# WattMeter_v3.net
KiCad netlist of a schematic drawn in EAGLE
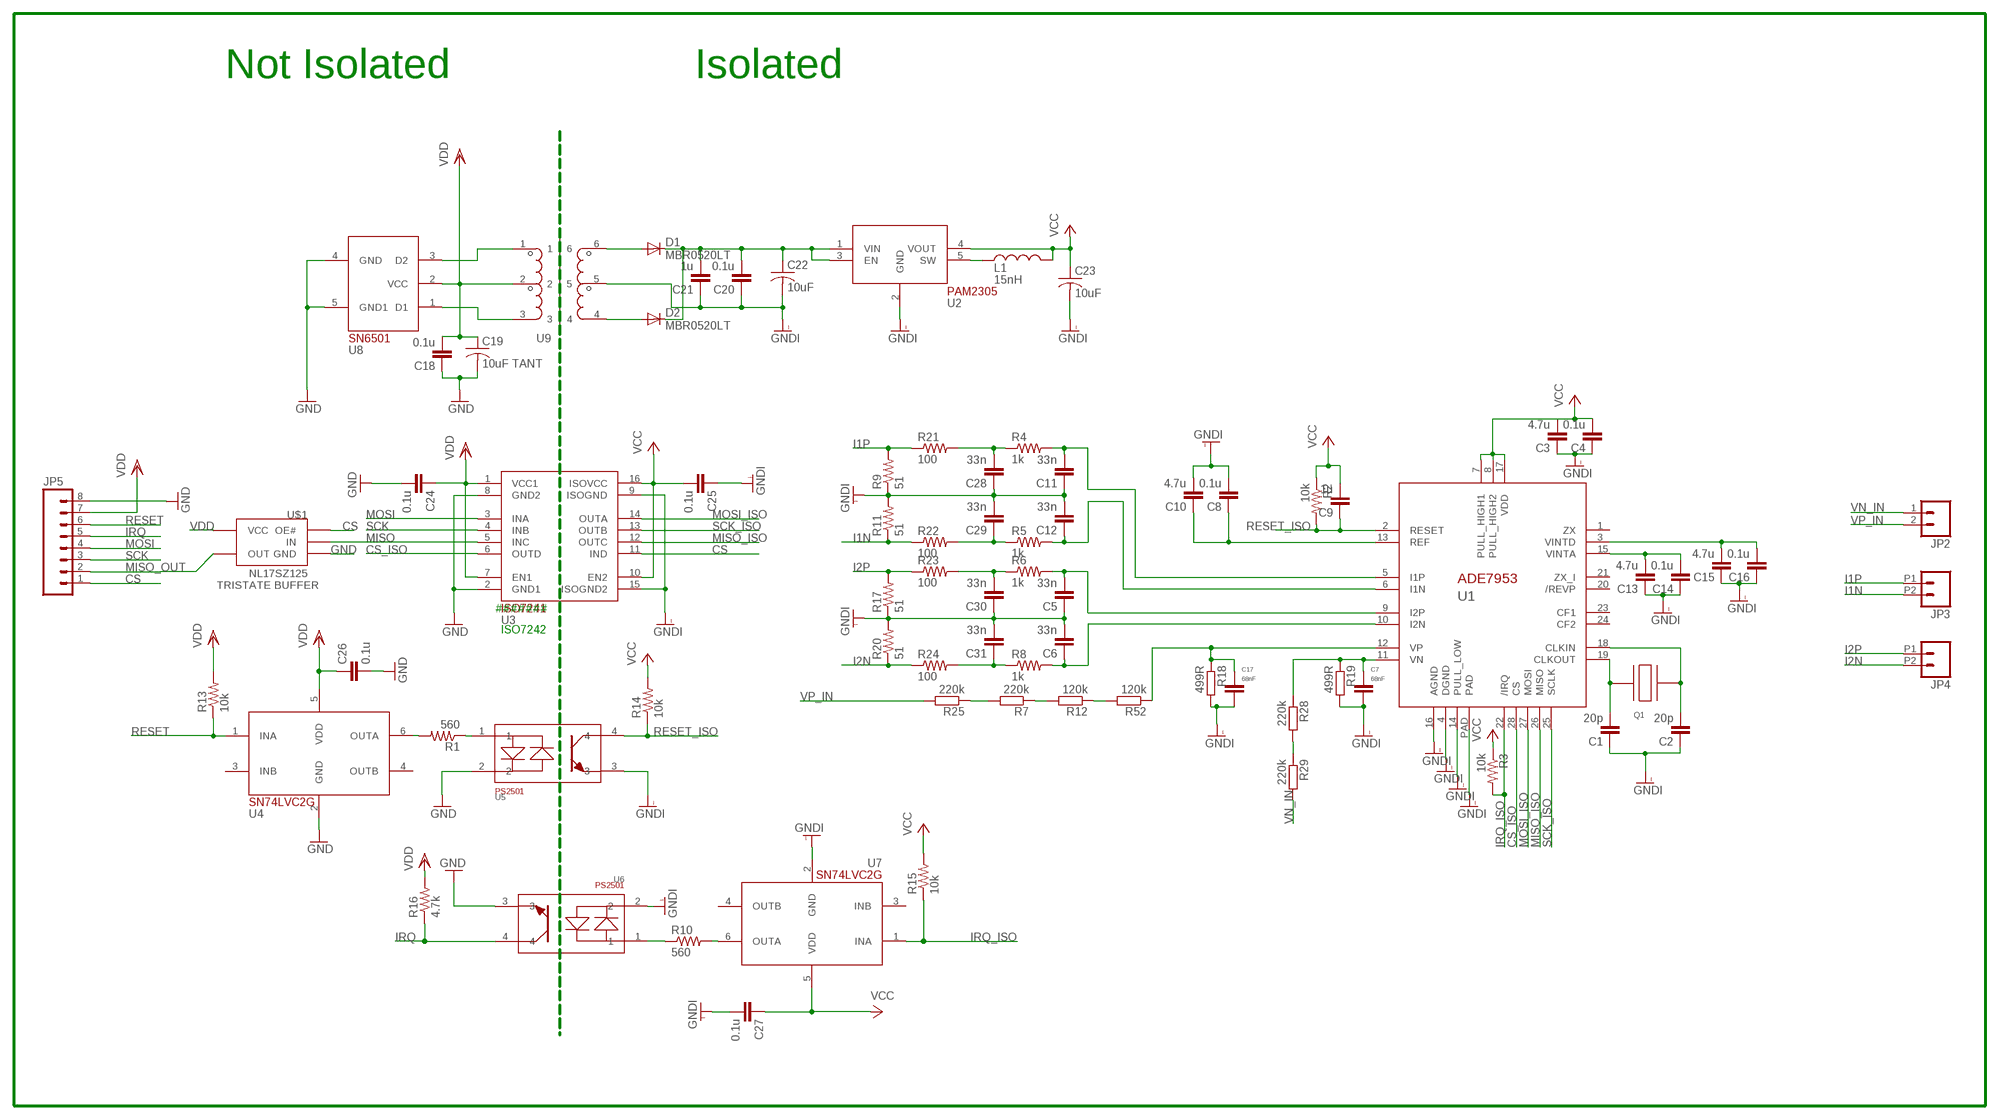
[diagram p0: schematic, sheet 1]

(export (version "E")
  (design (tool "Eeschema 10.0.6"))
  (components
    (comp (ref "C1")
      (value "20p")
      (footprint "eagle-import:0402-CAP")
      (libsource (lib "eagle-import") (part "0402-CAP"))
    )
    (comp (ref "C2")
      (value "20p")
      (footprint "eagle-import:0402-CAP")
      (libsource (lib "eagle-import") (part "0402-CAP"))
    )
    (comp (ref "C3")
      (value "4.7u")
      (footprint "eagle-import:0402-CAP")
      (libsource (lib "eagle-import") (part "0402-CAP"))
    )
    (comp (ref "C4")
      (value "0.1u")
      (footprint "eagle-import:0402-CAP")
      (libsource (lib "eagle-import") (part "0402-CAP"))
    )
    (comp (ref "C5")
      (value "33n")
      (footprint "eagle-import:0402-CAP")
      (libsource (lib "eagle-import") (part "0402-CAP"))
    )
    (comp (ref "C6")
      (value "33n")
      (footprint "eagle-import:0402-CAP")
      (libsource (lib "eagle-import") (part "0402-CAP"))
    )
    (comp (ref "C7")
      (value "68nF")
      (footprint "eagle-import:C0805K")
      (libsource (lib "eagle-import") (part "C-EUC0805K"))
    )
    (comp (ref "C8")
      (value "0.1u")
      (footprint "eagle-import:0402-CAP")
      (libsource (lib "eagle-import") (part "0402-CAP"))
    )
    (comp (ref "C9")
      (value "1u")
      (footprint "eagle-import:0402-CAP")
      (libsource (lib "eagle-import") (part "0402-CAP"))
    )
    (comp (ref "C10")
      (value "4.7u")
      (footprint "eagle-import:0402-CAP")
      (libsource (lib "eagle-import") (part "0402-CAP"))
    )
    (comp (ref "C11")
      (value "33n")
      (footprint "eagle-import:0402-CAP")
      (libsource (lib "eagle-import") (part "0402-CAP"))
    )
    (comp (ref "C12")
      (value "33n")
      (footprint "eagle-import:0402-CAP")
      (libsource (lib "eagle-import") (part "0402-CAP"))
    )
    (comp (ref "C13")
      (value "4.7u")
      (footprint "eagle-import:0402-CAP")
      (libsource (lib "eagle-import") (part "0402-CAP"))
    )
    (comp (ref "C14")
      (value "0.1u")
      (footprint "eagle-import:0402-CAP")
      (libsource (lib "eagle-import") (part "0402-CAP"))
    )
    (comp (ref "C15")
      (value "4.7u")
      (footprint "eagle-import:0402-CAP")
      (libsource (lib "eagle-import") (part "0402-CAP"))
    )
    (comp (ref "C16")
      (value "0.1u")
      (footprint "eagle-import:0402-CAP")
      (libsource (lib "eagle-import") (part "0402-CAP"))
    )
    (comp (ref "C17")
      (value "68nF")
      (footprint "eagle-import:C0805K")
      (libsource (lib "eagle-import") (part "C-EUC0805K"))
    )
    (comp (ref "C18")
      (value "0.1u")
      (footprint "eagle-import:0402-CAP")
      (libsource (lib "eagle-import") (part "0402-CAP"))
    )
    (comp (ref "C19")
      (value "10uF TANT")
      (footprint "eagle-import:C0603")
      (libsource (lib "eagle-import") (part "C-USC0603"))
    )
    (comp (ref "C20")
      (value "0.1u")
      (footprint "eagle-import:0402-CAP")
      (libsource (lib "eagle-import") (part "0402-CAP"))
    )
    (comp (ref "C21")
      (value "1u")
      (footprint "eagle-import:0402-CAP")
      (libsource (lib "eagle-import") (part "0402-CAP"))
    )
    (comp (ref "C22")
      (value "10uF")
      (footprint "eagle-import:C0603")
      (libsource (lib "eagle-import") (part "C-USC0603"))
    )
    (comp (ref "C23")
      (value "10uF")
      (footprint "eagle-import:C0603")
      (libsource (lib "eagle-import") (part "C-USC0603"))
    )
    (comp (ref "C24")
      (value "0.1u")
      (footprint "eagle-import:0402-CAP")
      (libsource (lib "eagle-import") (part "0402-CAP"))
    )
    (comp (ref "C25")
      (value "0.1u")
      (footprint "eagle-import:0402-CAP")
      (libsource (lib "eagle-import") (part "0402-CAP"))
    )
    (comp (ref "C26")
      (value "0.1u")
      (footprint "eagle-import:0402-CAP")
      (libsource (lib "eagle-import") (part "0402-CAP"))
    )
    (comp (ref "C27")
      (value "0.1u")
      (footprint "eagle-import:0402-CAP")
      (libsource (lib "eagle-import") (part "0402-CAP"))
    )
    (comp (ref "C28")
      (value "33n")
      (footprint "eagle-import:0402-CAP")
      (libsource (lib "eagle-import") (part "0402-CAP"))
    )
    (comp (ref "C29")
      (value "33n")
      (footprint "eagle-import:0402-CAP")
      (libsource (lib "eagle-import") (part "0402-CAP"))
    )
    (comp (ref "C30")
      (value "33n")
      (footprint "eagle-import:0402-CAP")
      (libsource (lib "eagle-import") (part "0402-CAP"))
    )
    (comp (ref "C31")
      (value "33n")
      (footprint "eagle-import:0402-CAP")
      (libsource (lib "eagle-import") (part "0402-CAP"))
    )
    (comp (ref "D1")
      (value "MBR0520LT")
      (footprint "eagle-import:SOD123")
      (libsource (lib "eagle-import") (part "MBR0520LT"))
    )
    (comp (ref "D2")
      (value "MBR0520LT")
      (footprint "eagle-import:SOD123")
      (libsource (lib "eagle-import") (part "MBR0520LT"))
    )
    (comp (ref "JP2")
      (value "M025MM")
      (footprint "eagle-import:SCREWTERMINAL-5MM-2")
      (libsource (lib "eagle-import") (part "M025MM"))
    )
    (comp (ref "JP3")
      (value "M022.54MM_SCREWTERM")
      (footprint "eagle-import:1X02_2.54_SCREWTERM")
      (libsource (lib "eagle-import") (part "M022.54MM_SCREWTERM"))
    )
    (comp (ref "JP4")
      (value "M022.54MM_SCREWTERM")
      (footprint "eagle-import:1X02_2.54_SCREWTERM")
      (libsource (lib "eagle-import") (part "M022.54MM_SCREWTERM"))
    )
    (comp (ref "JP5")
      (value "M08")
      (footprint "eagle-import:1X08_ROUND")
      (libsource (lib "eagle-import") (part "M08"))
    )
    (comp (ref "L1")
      (value "15nH")
      (footprint "eagle-import:0402-RES")
      (libsource (lib "eagle-import") (part "IND0402"))
    )
    (comp (ref "Q1")
      (value "QUARTZ_3.58M_2PIN")
      (footprint "eagle-import:HC-49S")
      (libsource (lib "eagle-import") (part "QUARTZ_3.58M_2PIN"))
    )
    (comp (ref "R1")
      (value "560")
      (footprint "eagle-import:0402-RES")
      (libsource (lib "eagle-import") (part "0402-RES"))
    )
    (comp (ref "R2")
      (value "10k")
      (footprint "eagle-import:0402-RES")
      (libsource (lib "eagle-import") (part "0402-RES"))
    )
    (comp (ref "R3")
      (value "10k")
      (footprint "eagle-import:0402-RES")
      (libsource (lib "eagle-import") (part "0402-RES"))
    )
    (comp (ref "R4")
      (value "1k")
      (footprint "eagle-import:0402-RES")
      (libsource (lib "eagle-import") (part "0402-RES"))
    )
    (comp (ref "R5")
      (value "1k")
      (footprint "eagle-import:0402-RES")
      (libsource (lib "eagle-import") (part "0402-RES"))
    )
    (comp (ref "R6")
      (value "1k")
      (footprint "eagle-import:0402-RES")
      (libsource (lib "eagle-import") (part "0402-RES"))
    )
    (comp (ref "R7")
      (value "220k")
      (footprint "eagle-import:R2010")
      (libsource (lib "eagle-import") (part "R-EU_R2010"))
    )
    (comp (ref "R8")
      (value "1k")
      (footprint "eagle-import:0402-RES")
      (libsource (lib "eagle-import") (part "0402-RES"))
    )
    (comp (ref "R9")
      (value "51")
      (footprint "eagle-import:0402-RES")
      (libsource (lib "eagle-import") (part "0402-RES"))
    )
    (comp (ref "R10")
      (value "560")
      (footprint "eagle-import:0402-RES")
      (libsource (lib "eagle-import") (part "0402-RES"))
    )
    (comp (ref "R11")
      (value "51")
      (footprint "eagle-import:0402-RES")
      (libsource (lib "eagle-import") (part "0402-RES"))
    )
    (comp (ref "R12")
      (value "120k")
      (footprint "eagle-import:M1206")
      (libsource (lib "eagle-import") (part "R-EU_M1206"))
    )
    (comp (ref "R13")
      (value "10k")
      (footprint "eagle-import:0402-RES")
      (libsource (lib "eagle-import") (part "0402-RES"))
    )
    (comp (ref "R14")
      (value "10k")
      (footprint "eagle-import:0402-RES")
      (libsource (lib "eagle-import") (part "0402-RES"))
    )
    (comp (ref "R15")
      (value "10k")
      (footprint "eagle-import:0402-RES")
      (libsource (lib "eagle-import") (part "0402-RES"))
    )
    (comp (ref "R16")
      (value "4.7k")
      (footprint "eagle-import:0402-RES")
      (libsource (lib "eagle-import") (part "0402-RES"))
    )
    (comp (ref "R17")
      (value "51")
      (footprint "eagle-import:0402-RES")
      (libsource (lib "eagle-import") (part "0402-RES"))
    )
    (comp (ref "R18")
      (value "499R")
      (footprint "eagle-import:C0805K@1")
      (libsource (lib "eagle-import") (part "R-EU_"))
    )
    (comp (ref "R19")
      (value "499R")
      (footprint "eagle-import:C0805K@1")
      (libsource (lib "eagle-import") (part "R-EU_"))
    )
    (comp (ref "R20")
      (value "51")
      (footprint "eagle-import:0402-RES")
      (libsource (lib "eagle-import") (part "0402-RES"))
    )
    (comp (ref "R21")
      (value "100")
      (footprint "eagle-import:0402-RES")
      (libsource (lib "eagle-import") (part "0402-RES"))
    )
    (comp (ref "R22")
      (value "100")
      (footprint "eagle-import:0402-RES")
      (libsource (lib "eagle-import") (part "0402-RES"))
    )
    (comp (ref "R23")
      (value "100")
      (footprint "eagle-import:0402-RES")
      (libsource (lib "eagle-import") (part "0402-RES"))
    )
    (comp (ref "R24")
      (value "100")
      (footprint "eagle-import:0402-RES")
      (libsource (lib "eagle-import") (part "0402-RES"))
    )
    (comp (ref "R25")
      (value "220k")
      (footprint "eagle-import:R2010")
      (libsource (lib "eagle-import") (part "R-EU_R2010"))
    )
    (comp (ref "R28")
      (value "220k")
      (footprint "eagle-import:R2010")
      (libsource (lib "eagle-import") (part "R-EU_R2010"))
    )
    (comp (ref "R29")
      (value "220k")
      (footprint "eagle-import:R2010")
      (libsource (lib "eagle-import") (part "R-EU_R2010"))
    )
    (comp (ref "R52")
      (value "120k")
      (footprint "eagle-import:M1206")
      (libsource (lib "eagle-import") (part "R-EU_M1206"))
    )
    (comp (ref "U$1")
      (value "BUFFER-NL17SZ125")
      (footprint "eagle-import:TSOP-5")
      (libsource (lib "eagle-import") (part "BUFFER-NL17SZ125"))
    )
    (comp (ref "U1")
      (value "ADE7953")
      (footprint "eagle-import:28-WFQFN")
      (libsource (lib "eagle-import") (part "ADE7953"))
    )
    (comp (ref "U2")
      (value "PAM2305")
      (footprint "eagle-import:TSOT25")
      (libsource (lib "eagle-import") (part "PAM2305"))
    )
    (comp (ref "U3")
      (value "ISO7241")
      (footprint "eagle-import:16-SOIC")
      (libsource (lib "eagle-import") (part "ISO7241"))
    )
    (comp (ref "U4")
      (value "SN74LVC")
      (footprint "eagle-import:DCKT")
      (libsource (lib "eagle-import") (part "SN74LVC"))
    )
    (comp (ref "U5")
      (value "PS2505")
      (footprint "eagle-import:4-SMD")
      (libsource (lib "eagle-import") (part "PS2505"))
    )
    (comp (ref "U6")
      (value "PS2505")
      (footprint "eagle-import:4-SMD")
      (libsource (lib "eagle-import") (part "PS2505"))
    )
    (comp (ref "U7")
      (value "SN74LVC")
      (footprint "eagle-import:DCKT")
      (libsource (lib "eagle-import") (part "SN74LVC"))
    )
    (comp (ref "U8")
      (value "SN6501")
      (footprint "eagle-import:SOT-23-5")
      (libsource (lib "eagle-import") (part "SN6501"))
    )
    (comp (ref "U9")
      (value "TRANSFO_3.3")
      (footprint "eagle-import:TRANSFO_3.3")
      (libsource (lib "eagle-import") (part "TRANSFO_3.3"))
    )
  )
  (nets
    (net (code "1") (name "/CS") (class "Default")
      (node (ref "JP5") (pin "1") (pinfunction "1_1") (pintype "passive"))
      (node (ref "U$1") (pin "1") (pinfunction "OE#_1") (pintype "bidirectional"))
      (node (ref "U3") (pin "11") (pinfunction "IND_11") (pintype "bidirectional"))
    )
    (net (code "2") (name "/CS_ISO") (class "Default")
      (node (ref "U1") (pin "28") (pinfunction "CS_28") (pintype "bidirectional"))
      (node (ref "U3") (pin "6") (pinfunction "OUTD_6") (pintype "bidirectional"))
    )
    (net (code "3") (name "/I1N") (class "Default")
      (node (ref "JP3") (pin "P2") (pinfunction "2_P2") (pintype "passive"))
      (node (ref "R11") (pin "1") (pinfunction "1_1") (pintype "passive"))
      (node (ref "R22") (pin "1") (pinfunction "1_1") (pintype "passive"))
    )
    (net (code "4") (name "/I1P") (class "Default")
      (node (ref "JP3") (pin "P1") (pinfunction "1_P1") (pintype "passive"))
      (node (ref "R21") (pin "1") (pinfunction "1_1") (pintype "passive"))
      (node (ref "R9") (pin "2") (pinfunction "2_2") (pintype "passive"))
    )
    (net (code "5") (name "/I2N") (class "Default")
      (node (ref "JP4") (pin "P2") (pinfunction "2_P2") (pintype "passive"))
      (node (ref "R20") (pin "1") (pinfunction "1_1") (pintype "passive"))
      (node (ref "R24") (pin "1") (pinfunction "1_1") (pintype "passive"))
    )
    (net (code "6") (name "/I2P") (class "Default")
      (node (ref "JP4") (pin "P1") (pinfunction "1_P1") (pintype "passive"))
      (node (ref "R17") (pin "2") (pinfunction "2_2") (pintype "passive"))
      (node (ref "R23") (pin "1") (pinfunction "1_1") (pintype "passive"))
    )
    (net (code "7") (name "/IRQ") (class "Default")
      (node (ref "JP5") (pin "5") (pinfunction "5_5") (pintype "passive"))
      (node (ref "R16") (pin "1") (pinfunction "1_1") (pintype "passive"))
      (node (ref "U6") (pin "4") (pinfunction "4_4") (pintype "bidirectional"))
    )
    (net (code "8") (name "/IRQ_ISO") (class "Default")
      (node (ref "R15") (pin "1") (pinfunction "1_1") (pintype "passive"))
      (node (ref "R3") (pin "2") (pinfunction "2_2") (pintype "passive"))
      (node (ref "U1") (pin "22") (pinfunction "/IRQ_22") (pintype "bidirectional"))
      (node (ref "U7") (pin "1") (pinfunction "INA_1") (pintype "bidirectional"))
    )
    (net (code "9") (name "/MISO") (class "Default")
      (node (ref "U$1") (pin "2") (pinfunction "IN_2") (pintype "bidirectional"))
      (node (ref "U3") (pin "5") (pinfunction "INC_5") (pintype "bidirectional"))
    )
    (net (code "10") (name "/MISO_ISO") (class "Default")
      (node (ref "U1") (pin "26") (pinfunction "MISO_26") (pintype "bidirectional"))
      (node (ref "U3") (pin "12") (pinfunction "OUTC_12") (pintype "bidirectional"))
    )
    (net (code "11") (name "/MISO_OUT") (class "Default")
      (node (ref "JP5") (pin "2") (pinfunction "2_2") (pintype "passive"))
      (node (ref "U$1") (pin "4") (pinfunction "OUT_4") (pintype "bidirectional"))
    )
    (net (code "12") (name "/MOSI") (class "Default")
      (node (ref "JP5") (pin "4") (pinfunction "4_4") (pintype "passive"))
      (node (ref "U3") (pin "3") (pinfunction "INA_3") (pintype "bidirectional"))
    )
    (net (code "13") (name "/MOSI_ISO") (class "Default")
      (node (ref "U1") (pin "27") (pinfunction "MOSI_27") (pintype "bidirectional"))
      (node (ref "U3") (pin "14") (pinfunction "OUTA_14") (pintype "bidirectional"))
    )
    (net (code "14") (name "/RESET") (class "Default")
      (node (ref "JP5") (pin "6") (pinfunction "6_6") (pintype "passive"))
      (node (ref "R13") (pin "1") (pinfunction "1_1") (pintype "passive"))
      (node (ref "U4") (pin "1") (pinfunction "INA_1") (pintype "bidirectional"))
    )
    (net (code "15") (name "/RESET_ISO") (class "Default")
      (node (ref "C9") (pin "1") (pinfunction "1_1") (pintype "passive"))
      (node (ref "R14") (pin "1") (pinfunction "1_1") (pintype "passive"))
      (node (ref "R2") (pin "2") (pinfunction "2_2") (pintype "passive"))
      (node (ref "U1") (pin "2") (pinfunction "RESET_2") (pintype "bidirectional"))
      (node (ref "U5") (pin "4") (pinfunction "4_4") (pintype "bidirectional"))
    )
    (net (code "16") (name "/SCK") (class "Default")
      (node (ref "JP5") (pin "3") (pinfunction "3_3") (pintype "passive"))
      (node (ref "U3") (pin "4") (pinfunction "INB_4") (pintype "bidirectional"))
    )
    (net (code "17") (name "/SCK_ISO") (class "Default")
      (node (ref "U1") (pin "25") (pinfunction "SCLK_25") (pintype "bidirectional"))
      (node (ref "U3") (pin "13") (pinfunction "OUTB_13") (pintype "bidirectional"))
    )
    (net (code "18") (name "/VN_IN") (class "Default")
      (node (ref "JP2") (pin "1") (pinfunction "1_1") (pintype "passive"))
      (node (ref "R29") (pin "2") (pinfunction "2_2") (pintype "passive"))
    )
    (net (code "19") (name "/VP_IN") (class "Default")
      (node (ref "JP2") (pin "2") (pinfunction "2_2") (pintype "passive"))
      (node (ref "R25") (pin "2") (pinfunction "2_2") (pintype "passive"))
    )
    (net (code "20") (name "GND") (class "Default")
      (node (ref "C18") (pin "1") (pinfunction "1_1") (pintype "passive"))
      (node (ref "C19") (pin "2") (pinfunction "2_2") (pintype "passive"))
      (node (ref "C24") (pin "2") (pinfunction "2_2") (pintype "passive"))
      (node (ref "C26") (pin "2") (pinfunction "2_2") (pintype "passive"))
      (node (ref "JP5") (pin "8") (pinfunction "8_8") (pintype "passive"))
      (node (ref "U$1") (pin "3") (pinfunction "GND_3") (pintype "bidirectional"))
      (node (ref "U3") (pin "2") (pinfunction "GND1_2") (pintype "bidirectional"))
      (node (ref "U3") (pin "8") (pinfunction "GND2_8") (pintype "bidirectional"))
      (node (ref "U4") (pin "2") (pinfunction "GND_2") (pintype "bidirectional"))
      (node (ref "U5") (pin "2") (pinfunction "2_2") (pintype "bidirectional"))
      (node (ref "U6") (pin "3") (pinfunction "3_3") (pintype "bidirectional"))
      (node (ref "U8") (pin "4") (pinfunction "GND_4") (pintype "bidirectional"))
      (node (ref "U8") (pin "5") (pinfunction "GND1_5") (pintype "bidirectional"))
    )
    (net (code "21") (name "GNDI") (class "Default")
      (node (ref "C1") (pin "1") (pinfunction "1_1") (pintype "passive"))
      (node (ref "C10") (pin "2") (pinfunction "2_2") (pintype "passive"))
      (node (ref "C11") (pin "1") (pinfunction "1_1") (pintype "passive"))
      (node (ref "C12") (pin "2") (pinfunction "2_2") (pintype "passive"))
      (node (ref "C13") (pin "1") (pinfunction "1_1") (pintype "passive"))
      (node (ref "C14") (pin "1") (pinfunction "1_1") (pintype "passive"))
      (node (ref "C15") (pin "1") (pinfunction "1_1") (pintype "passive"))
      (node (ref "C16") (pin "1") (pinfunction "1_1") (pintype "passive"))
      (node (ref "C17") (pin "2") (pinfunction "2_2") (pintype "passive"))
      (node (ref "C2") (pin "1") (pinfunction "1_1") (pintype "passive"))
      (node (ref "C20") (pin "1") (pinfunction "1_1") (pintype "passive"))
      (node (ref "C21") (pin "1") (pinfunction "1_1") (pintype "passive"))
      (node (ref "C22") (pin "2") (pinfunction "2_2") (pintype "passive"))
      (node (ref "C23") (pin "2") (pinfunction "2_2") (pintype "passive"))
      (node (ref "C25") (pin "1") (pinfunction "1_1") (pintype "passive"))
      (node (ref "C27") (pin "2") (pinfunction "2_2") (pintype "passive"))
      (node (ref "C28") (pin "1") (pinfunction "1_1") (pintype "passive"))
      (node (ref "C29") (pin "2") (pinfunction "2_2") (pintype "passive"))
      (node (ref "C3") (pin "1") (pinfunction "1_1") (pintype "passive"))
      (node (ref "C30") (pin "1") (pinfunction "1_1") (pintype "passive"))
      (node (ref "C31") (pin "2") (pinfunction "2_2") (pintype "passive"))
      (node (ref "C4") (pin "1") (pinfunction "1_1") (pintype "passive"))
      (node (ref "C5") (pin "1") (pinfunction "1_1") (pintype "passive"))
      (node (ref "C6") (pin "2") (pinfunction "2_2") (pintype "passive"))
      (node (ref "C7") (pin "2") (pinfunction "2_2") (pintype "passive"))
      (node (ref "C8") (pin "2") (pinfunction "2_2") (pintype "passive"))
      (node (ref "R11") (pin "2") (pinfunction "2_2") (pintype "passive"))
      (node (ref "R17") (pin "1") (pinfunction "1_1") (pintype "passive"))
      (node (ref "R18") (pin "2") (pinfunction "2_2") (pintype "passive"))
      (node (ref "R19") (pin "2") (pinfunction "2_2") (pintype "passive"))
      (node (ref "R20") (pin "2") (pinfunction "2_2") (pintype "passive"))
      (node (ref "R9") (pin "1") (pinfunction "1_1") (pintype "passive"))
      (node (ref "U1") (pin "14") (pinfunction "PULL_LOW_14") (pintype "bidirectional"))
      (node (ref "U1") (pin "16") (pinfunction "AGND_16") (pintype "bidirectional"))
      (node (ref "U1") (pin "4") (pinfunction "DGND_4") (pintype "bidirectional"))
      (node (ref "U1") (pin "PAD") (pinfunction "PAD_PAD") (pintype "bidirectional"))
      (node (ref "U2") (pin "2") (pinfunction "GND_2") (pintype "bidirectional"))
      (node (ref "U3") (pin "15") (pinfunction "ISOGND2_15") (pintype "bidirectional"))
      (node (ref "U3") (pin "9") (pinfunction "ISOGND_9") (pintype "bidirectional"))
      (node (ref "U5") (pin "3") (pinfunction "3_3") (pintype "bidirectional"))
      (node (ref "U6") (pin "2") (pinfunction "2_2") (pintype "bidirectional"))
      (node (ref "U7") (pin "2") (pinfunction "GND_2") (pintype "bidirectional"))
      (node (ref "U9") (pin "5") (pinfunction "5_5") (pintype "bidirectional"))
    )
    (net (code "22") (name "Net-(C28-Pad2)") (class "Default")
      (node (ref "C28") (pin "2") (pinfunction "2_2") (pintype "passive"))
      (node (ref "R21") (pin "2") (pinfunction "2_2") (pintype "passive"))
      (node (ref "R4") (pin "1") (pinfunction "1_1") (pintype "passive"))
    )
    (net (code "23") (name "Net-(C29-Pad1)") (class "Default")
      (node (ref "C29") (pin "1") (pinfunction "1_1") (pintype "passive"))
      (node (ref "R22") (pin "2") (pinfunction "2_2") (pintype "passive"))
      (node (ref "R5") (pin "1") (pinfunction "1_1") (pintype "passive"))
    )
    (net (code "24") (name "Net-(C30-Pad2)") (class "Default")
      (node (ref "C30") (pin "2") (pinfunction "2_2") (pintype "passive"))
      (node (ref "R23") (pin "2") (pinfunction "2_2") (pintype "passive"))
      (node (ref "R6") (pin "1") (pinfunction "1_1") (pintype "passive"))
    )
    (net (code "25") (name "Net-(C31-Pad1)") (class "Default")
      (node (ref "C31") (pin "1") (pinfunction "1_1") (pintype "passive"))
      (node (ref "R24") (pin "2") (pinfunction "2_2") (pintype "passive"))
      (node (ref "R8") (pin "1") (pinfunction "1_1") (pintype "passive"))
    )
    (net (code "26") (name "Net-(D1-PadA)") (class "Default")
      (node (ref "D1") (pin "A") (pinfunction "A_A") (pintype "passive"))
      (node (ref "U9") (pin "6") (pinfunction "6_6") (pintype "bidirectional"))
    )
    (net (code "27") (name "Net-(D2-PadA)") (class "Default")
      (node (ref "D2") (pin "A") (pinfunction "A_A") (pintype "passive"))
      (node (ref "U9") (pin "4") (pinfunction "4_4") (pintype "bidirectional"))
    )
    (net (code "28") (name "Net-(R1-Pad1)") (class "Default")
      (node (ref "R1") (pin "1") (pinfunction "1_1") (pintype "passive"))
      (node (ref "U5") (pin "1") (pinfunction "1_1") (pintype "bidirectional"))
    )
    (net (code "29") (name "Net-(R10-Pad1)") (class "Default")
      (node (ref "R10") (pin "1") (pinfunction "1_1") (pintype "passive"))
      (node (ref "U6") (pin "1") (pinfunction "1_1") (pintype "bidirectional"))
    )
    (net (code "30") (name "Net-(R12-Pad1)") (class "Default")
      (node (ref "R12") (pin "1") (pinfunction "1_1") (pintype "passive"))
      (node (ref "R52") (pin "2") (pinfunction "2_2") (pintype "passive"))
    )
    (net (code "31") (name "Net-(R12-Pad2)") (class "Default")
      (node (ref "R12") (pin "2") (pinfunction "2_2") (pintype "passive"))
      (node (ref "R7") (pin "1") (pinfunction "1_1") (pintype "passive"))
    )
    (net (code "32") (name "Net-(R25-Pad1)") (class "Default")
      (node (ref "R25") (pin "1") (pinfunction "1_1") (pintype "passive"))
      (node (ref "R7") (pin "2") (pinfunction "2_2") (pintype "passive"))
    )
    (net (code "33") (name "Net-(R28-Pad2)") (class "Default")
      (node (ref "R28") (pin "2") (pinfunction "2_2") (pintype "passive"))
      (node (ref "R29") (pin "1") (pinfunction "1_1") (pintype "passive"))
    )
    (net (code "34") (name "Net-(U1-CLKIN)") (class "Default")
      (node (ref "C2") (pin "2") (pinfunction "2_2") (pintype "passive"))
      (node (ref "Q1") (pin "2") (pinfunction "2_2") (pintype "bidirectional"))
      (node (ref "U1") (pin "18") (pinfunction "CLKIN_18") (pintype "bidirectional"))
    )
    (net (code "35") (name "Net-(U1-CLKOUT)") (class "Default")
      (node (ref "C1") (pin "2") (pinfunction "2_2") (pintype "passive"))
      (node (ref "Q1") (pin "1") (pinfunction "1_1") (pintype "bidirectional"))
      (node (ref "U1") (pin "19") (pinfunction "CLKOUT_19") (pintype "bidirectional"))
    )
    (net (code "36") (name "Net-(U1-I1N)") (class "Default")
      (node (ref "C12") (pin "1") (pinfunction "1_1") (pintype "passive"))
      (node (ref "R5") (pin "2") (pinfunction "2_2") (pintype "passive"))
      (node (ref "U1") (pin "6") (pinfunction "I1N_6") (pintype "bidirectional"))
    )
    (net (code "37") (name "Net-(U1-I1P)") (class "Default")
      (node (ref "C11") (pin "2") (pinfunction "2_2") (pintype "passive"))
      (node (ref "R4") (pin "2") (pinfunction "2_2") (pintype "passive"))
      (node (ref "U1") (pin "5") (pinfunction "I1P_5") (pintype "bidirectional"))
    )
    (net (code "38") (name "Net-(U1-I2N)") (class "Default")
      (node (ref "C6") (pin "1") (pinfunction "1_1") (pintype "passive"))
      (node (ref "R8") (pin "2") (pinfunction "2_2") (pintype "passive"))
      (node (ref "U1") (pin "10") (pinfunction "I2N_10") (pintype "bidirectional"))
    )
    (net (code "39") (name "Net-(U1-I2P)") (class "Default")
      (node (ref "C5") (pin "2") (pinfunction "2_2") (pintype "passive"))
      (node (ref "R6") (pin "2") (pinfunction "2_2") (pintype "passive"))
      (node (ref "U1") (pin "9") (pinfunction "I2P_9") (pintype "bidirectional"))
    )
    (net (code "40") (name "Net-(U1-REF)") (class "Default")
      (node (ref "C10") (pin "1") (pinfunction "1_1") (pintype "passive"))
      (node (ref "C8") (pin "1") (pinfunction "1_1") (pintype "passive"))
      (node (ref "U1") (pin "13") (pinfunction "REF_13") (pintype "bidirectional"))
    )
    (net (code "41") (name "Net-(U1-VINTA)") (class "Default")
      (node (ref "C13") (pin "2") (pinfunction "2_2") (pintype "passive"))
      (node (ref "C14") (pin "2") (pinfunction "2_2") (pintype "passive"))
      (node (ref "U1") (pin "15") (pinfunction "VINTA_15") (pintype "bidirectional"))
    )
    (net (code "42") (name "Net-(U1-VINTD)") (class "Default")
      (node (ref "C15") (pin "2") (pinfunction "2_2") (pintype "passive"))
      (node (ref "C16") (pin "2") (pinfunction "2_2") (pintype "passive"))
      (node (ref "U1") (pin "3") (pinfunction "VINTD_3") (pintype "bidirectional"))
    )
    (net (code "43") (name "Net-(U1-VN)") (class "Default")
      (node (ref "C7") (pin "1") (pinfunction "1_1") (pintype "passive"))
      (node (ref "R19") (pin "1") (pinfunction "1_1") (pintype "passive"))
      (node (ref "R28") (pin "1") (pinfunction "1_1") (pintype "passive"))
      (node (ref "U1") (pin "11") (pinfunction "VN_11") (pintype "bidirectional"))
    )
    (net (code "44") (name "Net-(U1-VP)") (class "Default")
      (node (ref "C17") (pin "1") (pinfunction "1_1") (pintype "passive"))
      (node (ref "R18") (pin "1") (pinfunction "1_1") (pintype "passive"))
      (node (ref "R52") (pin "1") (pinfunction "1_1") (pintype "passive"))
      (node (ref "U1") (pin "12") (pinfunction "VP_12") (pintype "bidirectional"))
    )
    (net (code "45") (name "Net-(U2-EN)") (class "Default")
      (node (ref "C20") (pin "2") (pinfunction "2_2") (pintype "passive"))
      (node (ref "C21") (pin "2") (pinfunction "2_2") (pintype "passive"))
      (node (ref "C22") (pin "1") (pinfunction "1_1") (pintype "passive"))
      (node (ref "D1") (pin "C") (pinfunction "C_C") (pintype "passive"))
      (node (ref "D2") (pin "C") (pinfunction "C_C") (pintype "passive"))
      (node (ref "U2") (pin "1") (pinfunction "VIN_1") (pintype "bidirectional"))
      (node (ref "U2") (pin "3") (pinfunction "EN_3") (pintype "bidirectional"))
    )
    (net (code "46") (name "Net-(U2-SW)") (class "Default")
      (node (ref "L1") (pin "1") (pinfunction "1_1") (pintype "bidirectional"))
      (node (ref "U2") (pin "5") (pinfunction "SW_5") (pintype "bidirectional"))
    )
    (net (code "47") (name "Net-(U4-OUTA)") (class "Default")
      (node (ref "R1") (pin "2") (pinfunction "2_2") (pintype "passive"))
      (node (ref "U4") (pin "6") (pinfunction "OUTA_6") (pintype "bidirectional"))
    )
    (net (code "48") (name "Net-(U7-OUTA)") (class "Default")
      (node (ref "R10") (pin "2") (pinfunction "2_2") (pintype "passive"))
      (node (ref "U7") (pin "6") (pinfunction "OUTA_6") (pintype "bidirectional"))
    )
    (net (code "49") (name "Net-(U8-D1)") (class "Default")
      (node (ref "U8") (pin "1") (pinfunction "D1_1") (pintype "bidirectional"))
      (node (ref "U9") (pin "3") (pinfunction "3_3") (pintype "bidirectional"))
    )
    (net (code "50") (name "Net-(U8-D2)") (class "Default")
      (node (ref "U8") (pin "3") (pinfunction "D2_3") (pintype "bidirectional"))
      (node (ref "U9") (pin "1") (pinfunction "1_1") (pintype "bidirectional"))
    )
    (net (code "51") (name "VCC") (class "Default")
      (node (ref "C23") (pin "1") (pinfunction "1_1") (pintype "passive"))
      (node (ref "C25") (pin "2") (pinfunction "2_2") (pintype "passive"))
      (node (ref "C27") (pin "1") (pinfunction "1_1") (pintype "passive"))
      (node (ref "C3") (pin "2") (pinfunction "2_2") (pintype "passive"))
      (node (ref "C4") (pin "2") (pinfunction "2_2") (pintype "passive"))
      (node (ref "C9") (pin "2") (pinfunction "2_2") (pintype "passive"))
      (node (ref "L1") (pin "2") (pinfunction "2_2") (pintype "bidirectional"))
      (node (ref "R14") (pin "2") (pinfunction "2_2") (pintype "passive"))
      (node (ref "R15") (pin "2") (pinfunction "2_2") (pintype "passive"))
      (node (ref "R2") (pin "1") (pinfunction "1_1") (pintype "passive"))
      (node (ref "R3") (pin "1") (pinfunction "1_1") (pintype "passive"))
      (node (ref "U1") (pin "17") (pinfunction "VDD_17") (pintype "bidirectional"))
      (node (ref "U1") (pin "7") (pinfunction "PULL_HIGH1_7") (pintype "bidirectional"))
      (node (ref "U1") (pin "8") (pinfunction "PULL_HIGH2_8") (pintype "bidirectional"))
      (node (ref "U2") (pin "4") (pinfunction "VOUT_4") (pintype "bidirectional"))
      (node (ref "U3") (pin "10") (pinfunction "EN2_10") (pintype "bidirectional"))
      (node (ref "U3") (pin "16") (pinfunction "ISOVCC_16") (pintype "bidirectional"))
      (node (ref "U7") (pin "5") (pinfunction "VDD_5") (pintype "bidirectional"))
    )
    (net (code "52") (name "VDD") (class "Default")
      (node (ref "C18") (pin "2") (pinfunction "2_2") (pintype "passive"))
      (node (ref "C19") (pin "1") (pinfunction "1_1") (pintype "passive"))
      (node (ref "C24") (pin "1") (pinfunction "1_1") (pintype "passive"))
      (node (ref "C26") (pin "1") (pinfunction "1_1") (pintype "passive"))
      (node (ref "JP5") (pin "7") (pinfunction "7_7") (pintype "passive"))
      (node (ref "R13") (pin "2") (pinfunction "2_2") (pintype "passive"))
      (node (ref "R16") (pin "2") (pinfunction "2_2") (pintype "passive"))
      (node (ref "U$1") (pin "5") (pinfunction "VCC_5") (pintype "bidirectional"))
      (node (ref "U3") (pin "1") (pinfunction "VCC1_1") (pintype "bidirectional"))
      (node (ref "U3") (pin "7") (pinfunction "EN1_7") (pintype "bidirectional"))
      (node (ref "U4") (pin "5") (pinfunction "VDD_5") (pintype "bidirectional"))
      (node (ref "U8") (pin "2") (pinfunction "VCC_2") (pintype "bidirectional"))
      (node (ref "U9") (pin "2") (pinfunction "2_2") (pintype "bidirectional"))
    )
    (net (code "53") (name "unconnected-(U1-CF1-Pad23)") (class "Default")
      (node (ref "U1") (pin "23") (pinfunction "CF1_23") (pintype "bidirectional"))
    )
    (net (code "54") (name "unconnected-(U1-CF2-Pad24)") (class "Default")
      (node (ref "U1") (pin "24") (pinfunction "CF2_24") (pintype "bidirectional"))
    )
    (net (code "55") (name "unconnected-(U1-ZX-Pad1)") (class "Default")
      (node (ref "U1") (pin "1") (pinfunction "ZX_1") (pintype "bidirectional"))
    )
    (net (code "56") (name "unconnected-(U1-ZX_I-Pad21)") (class "Default")
      (node (ref "U1") (pin "21") (pinfunction "ZX_I_21") (pintype "bidirectional"))
    )
    (net (code "57") (name "unconnected-(U1-{slash}REVP-Pad20)") (class "Default")
      (node (ref "U1") (pin "20") (pinfunction "/REVP_20") (pintype "bidirectional"))
    )
    (net (code "58") (name "unconnected-(U4-INB-Pad3)") (class "Default")
      (node (ref "U4") (pin "3") (pinfunction "INB_3") (pintype "bidirectional"))
    )
    (net (code "59") (name "unconnected-(U4-OUTB-Pad4)") (class "Default")
      (node (ref "U4") (pin "4") (pinfunction "OUTB_4") (pintype "bidirectional"))
    )
    (net (code "60") (name "unconnected-(U7-INB-Pad3)") (class "Default")
      (node (ref "U7") (pin "3") (pinfunction "INB_3") (pintype "bidirectional"))
    )
    (net (code "61") (name "unconnected-(U7-OUTB-Pad4)") (class "Default")
      (node (ref "U7") (pin "4") (pinfunction "OUTB_4") (pintype "bidirectional"))
    )
  )
)
